# usb_ttl.net
KiCad netlist of a schematic drawn in Altium Designer
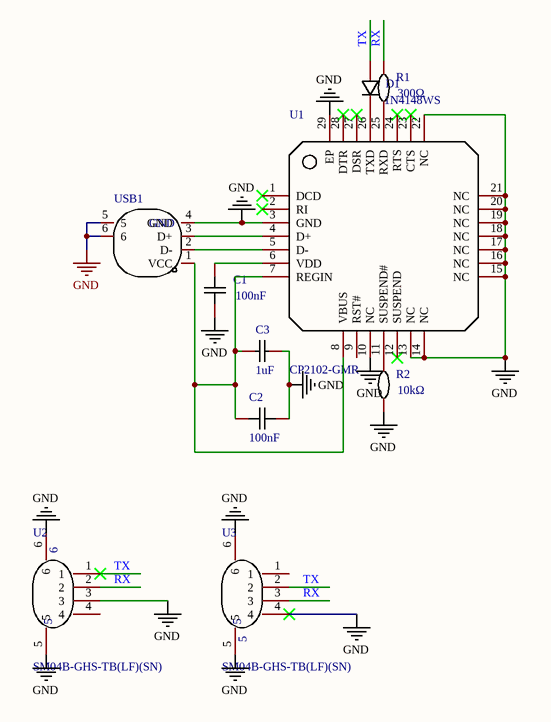
[diagram p0: usb_ttl.schdoc]

(export (version "E")
  (design (tool "Eeschema 10.0.6"))
  (components
    (comp (ref "C1")
      (value "100nF")
      (footprint "C0402")
      (description "容值:100nF;精度:±10%;额定电压:50V;材质(温度系数):X7R;")
      (fields
        (field (name "NAME") "100nF")
        (field (name "MANUFACTURER") "SAMSUNG(三星)")
        (field (name "MANUFACTURER PART") "CL05B104KB54PNC")
      )
      (libsource (lib "altium-import") (part "root_1_CL05B104KB54PNC_"))
    )
    (comp (ref "C2")
      (value "100nF")
      (footprint "C0603")
      (description "容值:100nF;精度:±10%;额定电压:50V;材质(温度系数):X7R;")
      (fields
        (field (name "NAME") "100nF")
        (field (name "MANUFACTURER") "YAGEO(国巨)")
        (field (name "MANUFACTURER PART") "CC0603KRX7R9BB104")
      )
      (libsource (lib "altium-import") (part "root_2_CC0603KRX7R9BB104_"))
    )
    (comp (ref "C3")
      (value "1uF")
      (footprint "C0603")
      (description "容值:1uF;精度:±10%;额定电压:50V;材质(温度系数):X5R;")
      (fields
        (field (name "NAME") "1uF")
        (field (name "MANUFACTURER") "SAMSUNG(三星)")
        (field (name "MANUFACTURER PART") "CL10A105KB8NNNC")
      )
      (libsource (lib "altium-import") (part "root_2_CL10A105KB8NNNC_"))
    )
    (comp (ref "D1")
      (value "1N4148WS")
      (footprint "SOD-323_L1.8-W1.3-LS2.5-RD")
      (fields (field (name "NAME") "1N4148WS") (field (name "MANUFACTURER") "CJ(江苏长电/长晶)"))
      (libsource (lib "altium-import") (part "root_1_1N4148WS_C2128_"))
    )
    (comp (ref "R1")
      (value "300Ω")
      (footprint "R0603")
      (description "电阻类型:厚膜电阻;阻值:300Ω;精度:±1%;功率:100mW;温度系数:±100ppm/℃;最大工作电压:75V;工作温度范围:-55℃~+155℃;")
      (fields
        (field (name "NAME") "300Ω")
        (field (name "MANUFACTURER") "UNI-ROYAL(厚声)")
        (field (name "MANUFACTURER PART") "0603WAF3000T5E")
      )
      (libsource (lib "altium-import") (part "root_1_0603WAF3000T5E_"))
    )
    (comp (ref "R2")
      (value "10kΩ")
      (footprint "R0402")
      (description "电阻类型:厚膜电阻;阻值:10kΩ;精度:±1%;功率:62.5mW;温度系数:±100ppm/℃;最大工作电压:50V;工作温度范围:-55℃~+155℃;")
      (fields
        (field (name "NAME") "10kΩ")
        (field (name "MANUFACTURER") "UNI-ROYAL(厚声)")
        (field (name "MANUFACTURER PART") "0402WGF1002TCE")
      )
      (libsource (lib "altium-import") (part "root_1_0402WGF1002TCE_"))
    )
    (comp (ref "U1")
      (value "CP2102-GMR")
      (footprint "WQFN-28_L5.0-W5.0-P0.50-BL-EP3.2")
      (description "类型:Transceiver;协议类别:USB;驱动器/接收器数:1/1;数据速率:1Mbps;")
      (fields (field (name "NAME") "CP2102-GMR") (field (name "MANUFACTURER") "SILICON LABS(芯科)"))
      (libsource (lib "altium-import") (part "root_0_CP2102-GMR_"))
    )
    (comp (ref "U2")
      (value "SM04B-GHS-TB(LF)(SN)")
      (footprint "CONN-SMD_4P-P1.25_SM04B-GHS-TB-LF-SN")
      (description "参考系列:GH;间距:1.25mm;插针结构:1x4P;排数:1;每排PIN数:4;行距:-;安装方式:-;触头材质:磷青铜;")
      (fields
        (field (name "NAME") "SM04B-GHS-TB(LF)(SN)")
        (field (name "MANUFACTURER") "JST")
        (field (name "NAME_1") "5")
        (field (name "NUMBER") "6")
      )
      (libsource (lib "altium-import") (part "root_3_SM04B-GHS-TB(LF)(SN)_"))
    )
    (comp (ref "U3")
      (value "SM04B-GHS-TB(LF)(SN)")
      (footprint "CONN-SMD_4P-P1.25_SM04B-GHS-TB-LF-SN")
      (description "参考系列:GH;间距:1.25mm;插针结构:1x4P;排数:1;每排PIN数:4;行距:-;安装方式:-;触头材质:磷青铜;")
      (fields
        (field (name "NAME") "SM04B-GHS-TB(LF)(SN)")
        (field (name "MANUFACTURER") "JST")
        (field (name "NAME_1") "5")
        (field (name "NUMBER") "5")
      )
      (libsource (lib "altium-import") (part "root_3_SM04B-GHS-TB(LF)(SN)_"))
    )
    (comp (ref "USB1")
      (value "917-P81A102ES60200")
      (footprint "USB-A-SMD_917-P81A102ES60200")
      (description "连接器类型:Type-A;标准:USB 2.0;公母:公头;触点数量:4;端口数量:1;安装方式:沉板;额定电流 - 电源:1.5A;工作温度范围:-;")
      (fields (field (name "MANUFACTURER") "精拓金") (field (name "NAME") "GND"))
      (libsource (lib "altium-import") (part "root_2_917-P81A102ES60200_"))
    )
  )
  (nets
    (net (code "1") (name "/RX") (class "Default")
      (node (ref "R1") (pin "2") (pinfunction "2_2") (pintype "passive"))
      (node (ref "U2") (pin "2") (pinfunction "2_2") (pintype "passive"))
      (node (ref "U3") (pin "3") (pinfunction "3_3") (pintype "passive"))
    )
    (net (code "2") (name "/TX") (class "Default")
      (node (ref "D1") (pin "2") (pinfunction "A_2") (pintype "passive"))
      (node (ref "U2") (pin "1") (pinfunction "1_1") (pintype "passive"))
      (node (ref "U3") (pin "2") (pinfunction "2_2") (pintype "passive"))
    )
    (net (code "3") (name "GND") (class "Default")
      (node (ref "C1") (pin "1") (pinfunction "1_1") (pintype "passive"))
      (node (ref "C2") (pin "1") (pinfunction "1_1") (pintype "passive"))
      (node (ref "C3") (pin "1") (pinfunction "1_1") (pintype "passive"))
      (node (ref "R2") (pin "1") (pinfunction "1_1") (pintype "passive"))
      (node (ref "U1") (pin "10") (pinfunction "NC_10") (pintype "passive"))
      (node (ref "U1") (pin "13") (pinfunction "NC_13") (pintype "passive"))
      (node (ref "U1") (pin "14") (pinfunction "NC_14") (pintype "passive"))
      (node (ref "U1") (pin "15") (pinfunction "NC_15") (pintype "passive"))
      (node (ref "U1") (pin "16") (pinfunction "NC_16") (pintype "passive"))
      (node (ref "U1") (pin "17") (pinfunction "NC_17") (pintype "passive"))
      (node (ref "U1") (pin "18") (pinfunction "NC_18") (pintype "passive"))
      (node (ref "U1") (pin "19") (pinfunction "NC_19") (pintype "passive"))
      (node (ref "U1") (pin "20") (pinfunction "NC_20") (pintype "passive"))
      (node (ref "U1") (pin "21") (pinfunction "NC_21") (pintype "passive"))
      (node (ref "U1") (pin "22") (pinfunction "NC_22") (pintype "passive"))
      (node (ref "U1") (pin "29") (pinfunction "EP_29") (pintype "passive"))
      (node (ref "U1") (pin "3") (pinfunction "GND_3") (pintype "passive"))
      (node (ref "U2") (pin "3") (pinfunction "3_3") (pintype "passive"))
      (node (ref "U2") (pin "5") (pinfunction "5_5") (pintype "passive"))
      (node (ref "U2") (pin "6") (pinfunction "6_6") (pintype "passive"))
      (node (ref "U3") (pin "4") (pinfunction "4_4") (pintype "passive"))
      (node (ref "U3") (pin "5") (pinfunction "5_5") (pintype "passive"))
      (node (ref "U3") (pin "6") (pinfunction "6_6") (pintype "passive"))
      (node (ref "USB1") (pin "4") (pinfunction "GND_4") (pintype "passive"))
      (node (ref "USB1") (pin "5") (pinfunction "5_5") (pintype "passive"))
      (node (ref "USB1") (pin "6") (pinfunction "6_6") (pintype "passive"))
    )
    (net (code "4") (name "Net-(D1-K)") (class "Default")
      (node (ref "D1") (pin "1") (pinfunction "K_1") (pintype "passive"))
      (node (ref "U1") (pin "26") (pinfunction "TXD_26") (pintype "passive"))
    )
    (net (code "5") (name "Net-(U1-D+)") (class "Default")
      (node (ref "U1") (pin "4") (pinfunction "D+_4") (pintype "passive"))
      (node (ref "USB1") (pin "3") (pinfunction "D+_3") (pintype "passive"))
    )
    (net (code "6") (name "Net-(U1-D-)") (class "Default")
      (node (ref "U1") (pin "5") (pinfunction "D-_5") (pintype "passive"))
      (node (ref "USB1") (pin "2") (pinfunction "D-_2") (pintype "passive"))
    )
    (net (code "7") (name "Net-(U1-REGIN)") (class "Default")
      (node (ref "C2") (pin "2") (pinfunction "2_2") (pintype "passive"))
      (node (ref "C3") (pin "2") (pinfunction "2_2") (pintype "passive"))
      (node (ref "U1") (pin "7") (pinfunction "REGIN_7") (pintype "passive"))
      (node (ref "U1") (pin "8") (pinfunction "VBUS_8") (pintype "passive"))
      (node (ref "USB1") (pin "1") (pinfunction "VCC_1") (pintype "passive"))
    )
    (net (code "8") (name "Net-(U1-RXD)") (class "Default")
      (node (ref "R1") (pin "1") (pinfunction "1_1") (pintype "passive"))
      (node (ref "U1") (pin "25") (pinfunction "RXD_25") (pintype "passive"))
    )
    (net (code "9") (name "Net-(U1-SUSPEND#)") (class "Default")
      (node (ref "R2") (pin "2") (pinfunction "2_2") (pintype "passive"))
      (node (ref "U1") (pin "11") (pinfunction "SUSPEND#_11") (pintype "passive"))
    )
    (net (code "10") (name "Net-(U1-VDD)") (class "Default")
      (node (ref "C1") (pin "2") (pinfunction "2_2") (pintype "passive"))
      (node (ref "U1") (pin "6") (pinfunction "VDD_6") (pintype "passive"))
    )
    (net (code "11") (name "unconnected-(U1-CTS-Pad23)") (class "Default")
      (node (ref "U1") (pin "23") (pinfunction "CTS_23") (pintype "passive+no_connect"))
    )
    (net (code "12") (name "unconnected-(U1-DCD-Pad1)") (class "Default")
      (node (ref "U1") (pin "1") (pinfunction "DCD_1") (pintype "passive+no_connect"))
    )
    (net (code "13") (name "unconnected-(U1-DSR-Pad27)") (class "Default")
      (node (ref "U1") (pin "27") (pinfunction "DSR_27") (pintype "passive+no_connect"))
    )
    (net (code "14") (name "unconnected-(U1-DTR-Pad28)") (class "Default")
      (node (ref "U1") (pin "28") (pinfunction "DTR_28") (pintype "passive+no_connect"))
    )
    (net (code "15") (name "unconnected-(U1-RI-Pad2)") (class "Default")
      (node (ref "U1") (pin "2") (pinfunction "RI_2") (pintype "passive+no_connect"))
    )
    (net (code "16") (name "unconnected-(U1-RST#-Pad9)") (class "Default")
      (node (ref "U1") (pin "9") (pinfunction "RST#_9") (pintype "passive"))
    )
    (net (code "17") (name "unconnected-(U1-RTS-Pad24)") (class "Default")
      (node (ref "U1") (pin "24") (pinfunction "RTS_24") (pintype "passive+no_connect"))
    )
    (net (code "18") (name "unconnected-(U1-SUSPEND-Pad12)") (class "Default")
      (node (ref "U1") (pin "12") (pinfunction "SUSPEND_12") (pintype "passive+no_connect"))
    )
    (net (code "19") (name "unconnected-(U2-Pad4)") (class "Default")
      (node (ref "U2") (pin "4") (pinfunction "4_4") (pintype "passive"))
    )
    (net (code "20") (name "unconnected-(U3-Pad1)") (class "Default")
      (node (ref "U3") (pin "1") (pinfunction "1_1") (pintype "passive"))
    )
  )
)
